# PG09__TEMP_BALANCER.net
KiCad netlist of a schematic drawn in Altium Designer
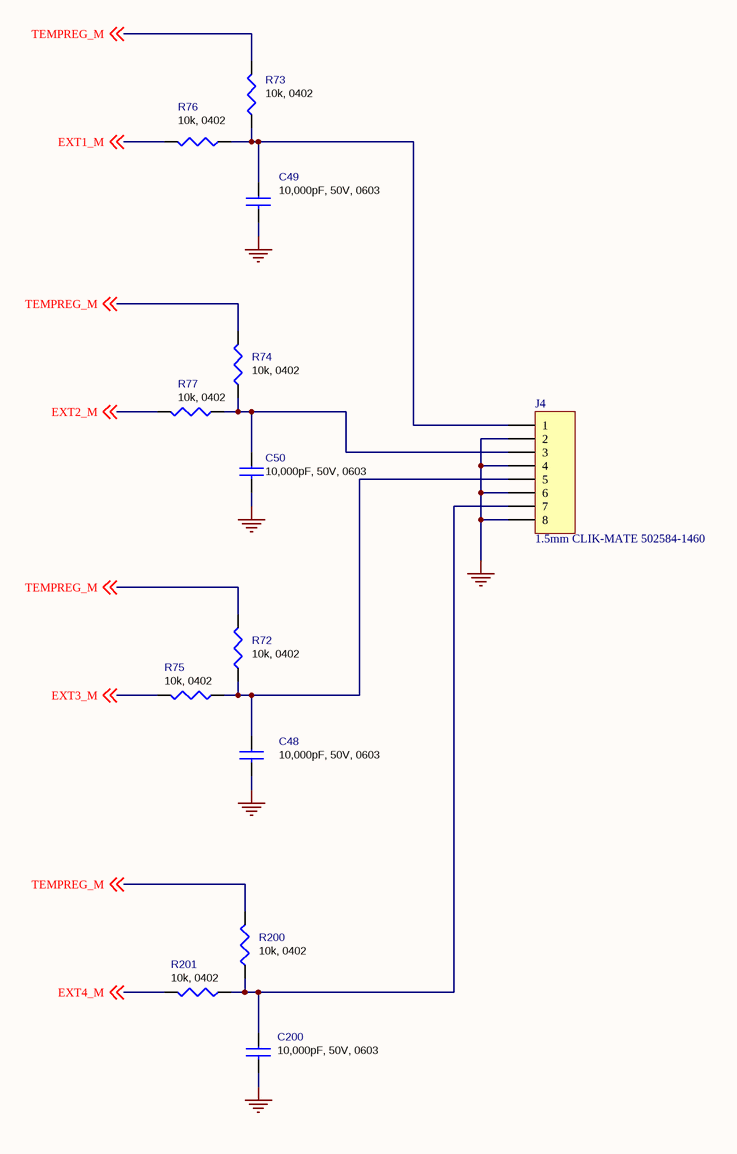
[diagram p0: PG09_ TEMP_BALANCER.SchDoc]

(export (version "E")
  (design (tool "Eeschema 10.0.6"))
  (components
    (comp (ref "C48")
      (value "10,000pF, 50V, 0603")
      (footprint "C0603")
      (description "CAP CER 10000PF 50V X7R 0603")
      (fields
        (field (name "MANUFACTURER") "TDK")
        (field (name "MANUFACTURER PART NUMBER") "CGA3E2X7R1H103K080AE")
      )
      (libsource (lib "*") (part "CAP-Generic-0603"))
    )
    (comp (ref "C49")
      (value "10,000pF, 50V, 0603")
      (footprint "C0603")
      (description "CAP CER 10000PF 50V X7R 0603")
      (fields
        (field (name "MANUFACTURER") "TDK")
        (field (name "MANUFACTURER PART NUMBER") "CGA3E2X7R1H103K080AE")
      )
      (libsource (lib "*") (part "CAP-Generic-0603"))
    )
    (comp (ref "C50")
      (value "10,000pF, 50V, 0603")
      (footprint "C0603")
      (description "CAP CER 10000PF 50V X7R 0603")
      (fields
        (field (name "MANUFACTURER") "TDK")
        (field (name "MANUFACTURER PART NUMBER") "CGA3E2X7R1H103K080AE")
      )
      (libsource (lib "*") (part "CAP-Generic-0603"))
    )
    (comp (ref "C200")
      (value "10,000pF, 50V, 0603")
      (footprint "C0603")
      (description "CAP CER 10000PF 50V X7R 0603")
      (fields
        (field (name "MANUFACTURER") "TDK")
        (field (name "MANUFACTURER PART NUMBER") "CGA3E2X7R1H103K080AE")
      )
      (libsource (lib "*") (part "CAP-Generic-0603"))
    )
    (comp (ref "J4")
      (value "1.5mm CLIK-MATE 502584-1460")
      (footprint "CONN8_1P5MM_SM")
      (description "CONN RCPT 8POS 0.059 TIN SMD")
      (fields (field (name "MANUFACTURER") "Molex") (field (name "MANUFACTURER PART NUMBER") "502584-0860"))
      (libsource (lib "Miscellaneous Connectors") (part "Header 8"))
    )
    (comp (ref "R72")
      (value "10k, 0402")
      (footprint "R0402")
      (description "RES SMD 10K OHM 1% 1/16W 0402")
      (fields
        (field (name "MANUFACTURER") "Vishay Dale")
        (field (name "MANUFACTURER PART NUMBER") "CRCW040210K0FKTD")
      )
      (libsource (lib "Miscellaneous Devices") (part "R-Generic-0402"))
    )
    (comp (ref "R73")
      (value "10k, 0402")
      (footprint "R0402")
      (description "RES SMD 10K OHM 1% 1/16W 0402")
      (fields
        (field (name "MANUFACTURER") "Vishay Dale")
        (field (name "MANUFACTURER PART NUMBER") "CRCW040210K0FKTD")
      )
      (libsource (lib "Miscellaneous Devices") (part "R-Generic-0402"))
    )
    (comp (ref "R74")
      (value "10k, 0402")
      (footprint "R0402")
      (description "RES SMD 10K OHM 1% 1/16W 0402")
      (fields
        (field (name "MANUFACTURER") "Vishay Dale")
        (field (name "MANUFACTURER PART NUMBER") "CRCW040210K0FKTD")
      )
      (libsource (lib "Miscellaneous Devices") (part "R-Generic-0402"))
    )
    (comp (ref "R75")
      (value "10k, 0402")
      (footprint "R0402")
      (description "RES SMD 10K OHM 1% 1/16W 0402")
      (fields
        (field (name "MANUFACTURER") "Vishay Dale")
        (field (name "MANUFACTURER PART NUMBER") "CRCW040210K0FKTD")
      )
      (libsource (lib "Miscellaneous Devices") (part "R-Generic-0402"))
    )
    (comp (ref "R76")
      (value "10k, 0402")
      (footprint "R0402")
      (description "RES SMD 10K OHM 1% 1/16W 0402")
      (fields
        (field (name "MANUFACTURER") "Vishay Dale")
        (field (name "MANUFACTURER PART NUMBER") "CRCW040210K0FKTD")
      )
      (libsource (lib "Miscellaneous Devices") (part "R-Generic-0402"))
    )
    (comp (ref "R77")
      (value "10k, 0402")
      (footprint "R0402")
      (description "RES SMD 10K OHM 1% 1/16W 0402")
      (fields
        (field (name "MANUFACTURER") "Vishay Dale")
        (field (name "MANUFACTURER PART NUMBER") "CRCW040210K0FKTD")
      )
      (libsource (lib "Miscellaneous Devices") (part "R-Generic-0402"))
    )
    (comp (ref "R200")
      (value "10k, 0402")
      (footprint "R0402")
      (description "RES SMD 10K OHM 1% 1/16W 0402")
      (fields
        (field (name "MANUFACTURER") "Vishay Dale")
        (field (name "MANUFACTURER PART NUMBER") "CRCW040210K0FKTD")
      )
      (libsource (lib "Miscellaneous Devices") (part "R-Generic-0402"))
    )
    (comp (ref "R201")
      (value "10k, 0402")
      (footprint "R0402")
      (description "RES SMD 10K OHM 1% 1/16W 0402")
      (fields
        (field (name "MANUFACTURER") "Vishay Dale")
        (field (name "MANUFACTURER PART NUMBER") "CRCW040210K0FKTD")
      )
      (libsource (lib "Miscellaneous Devices") (part "R-Generic-0402"))
    )
  )
  (nets
    (net (code "1") (name "EXT1_M") (class "Default")
      (node (ref "R76") (pin "2") (pinfunction "2_2") (pintype "passive"))
    )
    (net (code "2") (name "EXT2_M") (class "Default")
      (node (ref "R77") (pin "2") (pinfunction "2_2") (pintype "passive"))
    )
    (net (code "3") (name "EXT3_M") (class "Default")
      (node (ref "R75") (pin "2") (pinfunction "2_2") (pintype "passive"))
    )
    (net (code "4") (name "EXT4_M") (class "Default")
      (node (ref "R201") (pin "2") (pinfunction "2_2") (pintype "passive"))
    )
    (net (code "5") (name "GND") (class "Default")
      (node (ref "C200") (pin "2") (pinfunction "2_2") (pintype "passive"))
      (node (ref "C48") (pin "2") (pinfunction "2_2") (pintype "passive"))
      (node (ref "C49") (pin "2") (pinfunction "2_2") (pintype "passive"))
      (node (ref "C50") (pin "2") (pinfunction "2_2") (pintype "passive"))
      (node (ref "J4") (pin "2") (pinfunction "2_2") (pintype "passive"))
      (node (ref "J4") (pin "4") (pinfunction "4_4") (pintype "passive"))
      (node (ref "J4") (pin "6") (pinfunction "6_6") (pintype "passive"))
      (node (ref "J4") (pin "8") (pinfunction "8_8") (pintype "passive"))
    )
    (net (code "6") (name "Net-(C48-Pad1)") (class "Default")
      (node (ref "C48") (pin "1") (pinfunction "1_1") (pintype "passive"))
      (node (ref "J4") (pin "5") (pinfunction "5_5") (pintype "passive"))
      (node (ref "R72") (pin "1") (pinfunction "1_1") (pintype "passive"))
      (node (ref "R75") (pin "1") (pinfunction "1_1") (pintype "passive"))
    )
    (net (code "7") (name "Net-(C49-Pad1)") (class "Default")
      (node (ref "C49") (pin "1") (pinfunction "1_1") (pintype "passive"))
      (node (ref "J4") (pin "1") (pinfunction "1_1") (pintype "passive"))
      (node (ref "R73") (pin "1") (pinfunction "1_1") (pintype "passive"))
      (node (ref "R76") (pin "1") (pinfunction "1_1") (pintype "passive"))
    )
    (net (code "8") (name "Net-(C50-Pad1)") (class "Default")
      (node (ref "C50") (pin "1") (pinfunction "1_1") (pintype "passive"))
      (node (ref "J4") (pin "3") (pinfunction "3_3") (pintype "passive"))
      (node (ref "R74") (pin "1") (pinfunction "1_1") (pintype "passive"))
      (node (ref "R77") (pin "1") (pinfunction "1_1") (pintype "passive"))
    )
    (net (code "9") (name "Net-(C200-Pad1)") (class "Default")
      (node (ref "C200") (pin "1") (pinfunction "1_1") (pintype "passive"))
      (node (ref "J4") (pin "7") (pinfunction "7_7") (pintype "passive"))
      (node (ref "R200") (pin "1") (pinfunction "1_1") (pintype "passive"))
      (node (ref "R201") (pin "1") (pinfunction "1_1") (pintype "passive"))
    )
    (net (code "10") (name "TEMPREG_M") (class "Default")
      (node (ref "R200") (pin "2") (pinfunction "2_2") (pintype "passive"))
      (node (ref "R72") (pin "2") (pinfunction "2_2") (pintype "passive"))
      (node (ref "R73") (pin "2") (pinfunction "2_2") (pintype "passive"))
      (node (ref "R74") (pin "2") (pinfunction "2_2") (pintype "passive"))
    )
  )
)
